# connector-bottom-j1-1.net
KiCad netlist of a schematic drawn in Altium Designer
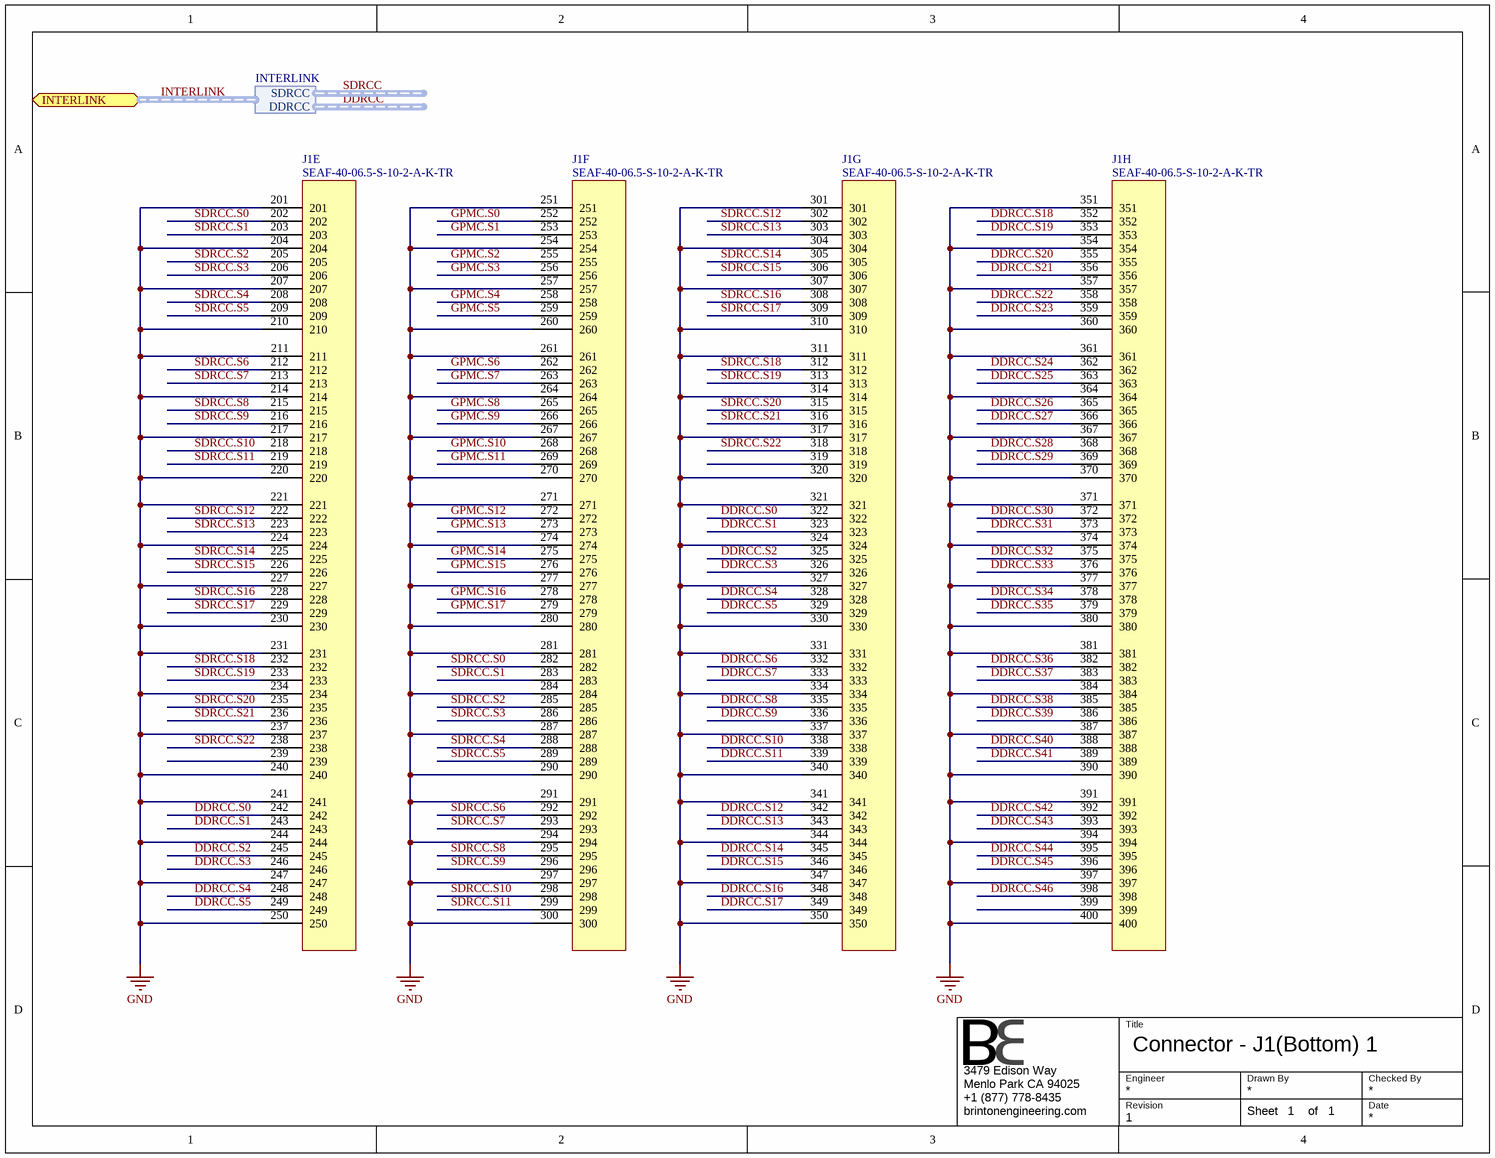
[diagram p0: connector-bottom-j1-1.SchDoc]

(export (version "E")
  (design (tool "Eeschema 10.0.6"))
  (components
    (comp (ref "J1")
      (value "SEAF-40-06.5-S-10-2-A-K-TR")
      (footprint "samtec:SEAF-40-06.5-S-10-2-A-K-TR")
      (description "Terminal Array Assembly, Surface Mount, 0.050\" Pitch, 400 Pins")
      (fields (field (name "MANUFACTURER") "Samtec"))
      (libsource (lib "samtec") (part "SEAF-40-06.5-S-10-2-A-K-TR"))
    )
  )
  (nets
    (net (code "3") (name "/DDRCC.S0") (class "Default")
      (node (ref "J1") (pin "242") (pinfunction "242_242") (pintype "passive"))
      (node (ref "J1") (pin "322") (pinfunction "322_322") (pintype "passive"))
    )
    (net (code "4") (name "/DDRCC.S1") (class "Default")
      (node (ref "J1") (pin "243") (pinfunction "243_243") (pintype "passive"))
      (node (ref "J1") (pin "323") (pinfunction "323_323") (pintype "passive"))
    )
    (net (code "5") (name "/DDRCC.S2") (class "Default")
      (node (ref "J1") (pin "245") (pinfunction "245_245") (pintype "passive"))
      (node (ref "J1") (pin "325") (pinfunction "325_325") (pintype "passive"))
    )
    (net (code "6") (name "/DDRCC.S3") (class "Default")
      (node (ref "J1") (pin "246") (pinfunction "246_246") (pintype "passive"))
      (node (ref "J1") (pin "326") (pinfunction "326_326") (pintype "passive"))
    )
    (net (code "7") (name "/DDRCC.S4") (class "Default")
      (node (ref "J1") (pin "248") (pinfunction "248_248") (pintype "passive"))
      (node (ref "J1") (pin "328") (pinfunction "328_328") (pintype "passive"))
    )
    (net (code "8") (name "/DDRCC.S5") (class "Default")
      (node (ref "J1") (pin "249") (pinfunction "249_249") (pintype "passive"))
      (node (ref "J1") (pin "329") (pinfunction "329_329") (pintype "passive"))
    )
    (net (code "9") (name "/DDRCC.S6") (class "Default")
      (node (ref "J1") (pin "332") (pinfunction "332_332") (pintype "passive"))
    )
    (net (code "10") (name "/DDRCC.S7") (class "Default")
      (node (ref "J1") (pin "333") (pinfunction "333_333") (pintype "passive"))
    )
    (net (code "11") (name "/DDRCC.S8") (class "Default")
      (node (ref "J1") (pin "335") (pinfunction "335_335") (pintype "passive"))
    )
    (net (code "12") (name "/DDRCC.S9") (class "Default")
      (node (ref "J1") (pin "336") (pinfunction "336_336") (pintype "passive"))
    )
    (net (code "13") (name "/DDRCC.S10") (class "Default")
      (node (ref "J1") (pin "338") (pinfunction "338_338") (pintype "passive"))
    )
    (net (code "14") (name "/DDRCC.S11") (class "Default")
      (node (ref "J1") (pin "339") (pinfunction "339_339") (pintype "passive"))
    )
    (net (code "15") (name "/DDRCC.S12") (class "Default")
      (node (ref "J1") (pin "342") (pinfunction "342_342") (pintype "passive"))
    )
    (net (code "16") (name "/DDRCC.S13") (class "Default")
      (node (ref "J1") (pin "343") (pinfunction "343_343") (pintype "passive"))
    )
    (net (code "17") (name "/DDRCC.S14") (class "Default")
      (node (ref "J1") (pin "345") (pinfunction "345_345") (pintype "passive"))
    )
    (net (code "18") (name "/DDRCC.S15") (class "Default")
      (node (ref "J1") (pin "346") (pinfunction "346_346") (pintype "passive"))
    )
    (net (code "19") (name "/DDRCC.S16") (class "Default")
      (node (ref "J1") (pin "348") (pinfunction "348_348") (pintype "passive"))
    )
    (net (code "20") (name "/DDRCC.S17") (class "Default")
      (node (ref "J1") (pin "349") (pinfunction "349_349") (pintype "passive"))
    )
    (net (code "21") (name "/DDRCC.S18") (class "Default")
      (node (ref "J1") (pin "352") (pinfunction "352_352") (pintype "passive"))
    )
    (net (code "22") (name "/DDRCC.S19") (class "Default")
      (node (ref "J1") (pin "353") (pinfunction "353_353") (pintype "passive"))
    )
    (net (code "23") (name "/DDRCC.S20") (class "Default")
      (node (ref "J1") (pin "355") (pinfunction "355_355") (pintype "passive"))
    )
    (net (code "24") (name "/DDRCC.S21") (class "Default")
      (node (ref "J1") (pin "356") (pinfunction "356_356") (pintype "passive"))
    )
    (net (code "25") (name "/DDRCC.S22") (class "Default")
      (node (ref "J1") (pin "358") (pinfunction "358_358") (pintype "passive"))
    )
    (net (code "26") (name "/DDRCC.S23") (class "Default")
      (node (ref "J1") (pin "359") (pinfunction "359_359") (pintype "passive"))
    )
    (net (code "27") (name "/DDRCC.S24") (class "Default")
      (node (ref "J1") (pin "362") (pinfunction "362_362") (pintype "passive"))
    )
    (net (code "28") (name "/DDRCC.S25") (class "Default")
      (node (ref "J1") (pin "363") (pinfunction "363_363") (pintype "passive"))
    )
    (net (code "29") (name "/DDRCC.S26") (class "Default")
      (node (ref "J1") (pin "365") (pinfunction "365_365") (pintype "passive"))
    )
    (net (code "30") (name "/DDRCC.S27") (class "Default")
      (node (ref "J1") (pin "366") (pinfunction "366_366") (pintype "passive"))
    )
    (net (code "31") (name "/DDRCC.S28") (class "Default")
      (node (ref "J1") (pin "368") (pinfunction "368_368") (pintype "passive"))
    )
    (net (code "32") (name "/DDRCC.S29") (class "Default")
      (node (ref "J1") (pin "369") (pinfunction "369_369") (pintype "passive"))
    )
    (net (code "33") (name "/DDRCC.S30") (class "Default")
      (node (ref "J1") (pin "372") (pinfunction "372_372") (pintype "passive"))
    )
    (net (code "34") (name "/DDRCC.S31") (class "Default")
      (node (ref "J1") (pin "373") (pinfunction "373_373") (pintype "passive"))
    )
    (net (code "35") (name "/DDRCC.S32") (class "Default")
      (node (ref "J1") (pin "375") (pinfunction "375_375") (pintype "passive"))
    )
    (net (code "36") (name "/DDRCC.S33") (class "Default")
      (node (ref "J1") (pin "376") (pinfunction "376_376") (pintype "passive"))
    )
    (net (code "37") (name "/DDRCC.S34") (class "Default")
      (node (ref "J1") (pin "378") (pinfunction "378_378") (pintype "passive"))
    )
    (net (code "38") (name "/DDRCC.S35") (class "Default")
      (node (ref "J1") (pin "379") (pinfunction "379_379") (pintype "passive"))
    )
    (net (code "39") (name "/DDRCC.S36") (class "Default")
      (node (ref "J1") (pin "382") (pinfunction "382_382") (pintype "passive"))
    )
    (net (code "40") (name "/DDRCC.S37") (class "Default")
      (node (ref "J1") (pin "383") (pinfunction "383_383") (pintype "passive"))
    )
    (net (code "41") (name "/DDRCC.S38") (class "Default")
      (node (ref "J1") (pin "385") (pinfunction "385_385") (pintype "passive"))
    )
    (net (code "42") (name "/DDRCC.S39") (class "Default")
      (node (ref "J1") (pin "386") (pinfunction "386_386") (pintype "passive"))
    )
    (net (code "43") (name "/DDRCC.S40") (class "Default")
      (node (ref "J1") (pin "388") (pinfunction "388_388") (pintype "passive"))
    )
    (net (code "44") (name "/DDRCC.S41") (class "Default")
      (node (ref "J1") (pin "389") (pinfunction "389_389") (pintype "passive"))
    )
    (net (code "45") (name "/DDRCC.S42") (class "Default")
      (node (ref "J1") (pin "392") (pinfunction "392_392") (pintype "passive"))
    )
    (net (code "46") (name "/DDRCC.S43") (class "Default")
      (node (ref "J1") (pin "393") (pinfunction "393_393") (pintype "passive"))
    )
    (net (code "47") (name "/DDRCC.S44") (class "Default")
      (node (ref "J1") (pin "395") (pinfunction "395_395") (pintype "passive"))
    )
    (net (code "48") (name "/DDRCC.S45") (class "Default")
      (node (ref "J1") (pin "396") (pinfunction "396_396") (pintype "passive"))
    )
    (net (code "49") (name "/DDRCC.S46") (class "Default")
      (node (ref "J1") (pin "398") (pinfunction "398_398") (pintype "passive"))
    )
    (net (code "51") (name "/GPMC.S0") (class "Default")
      (node (ref "J1") (pin "252") (pinfunction "252_252") (pintype "passive"))
    )
    (net (code "52") (name "/GPMC.S1") (class "Default")
      (node (ref "J1") (pin "253") (pinfunction "253_253") (pintype "passive"))
    )
    (net (code "53") (name "/GPMC.S2") (class "Default")
      (node (ref "J1") (pin "255") (pinfunction "255_255") (pintype "passive"))
    )
    (net (code "54") (name "/GPMC.S3") (class "Default")
      (node (ref "J1") (pin "256") (pinfunction "256_256") (pintype "passive"))
    )
    (net (code "55") (name "/GPMC.S4") (class "Default")
      (node (ref "J1") (pin "258") (pinfunction "258_258") (pintype "passive"))
    )
    (net (code "56") (name "/GPMC.S5") (class "Default")
      (node (ref "J1") (pin "259") (pinfunction "259_259") (pintype "passive"))
    )
    (net (code "57") (name "/GPMC.S6") (class "Default")
      (node (ref "J1") (pin "262") (pinfunction "262_262") (pintype "passive"))
    )
    (net (code "58") (name "/GPMC.S7") (class "Default")
      (node (ref "J1") (pin "263") (pinfunction "263_263") (pintype "passive"))
    )
    (net (code "59") (name "/GPMC.S8") (class "Default")
      (node (ref "J1") (pin "265") (pinfunction "265_265") (pintype "passive"))
    )
    (net (code "60") (name "/GPMC.S9") (class "Default")
      (node (ref "J1") (pin "266") (pinfunction "266_266") (pintype "passive"))
    )
    (net (code "61") (name "/GPMC.S10") (class "Default")
      (node (ref "J1") (pin "268") (pinfunction "268_268") (pintype "passive"))
    )
    (net (code "62") (name "/GPMC.S11") (class "Default")
      (node (ref "J1") (pin "269") (pinfunction "269_269") (pintype "passive"))
    )
    (net (code "63") (name "/GPMC.S12") (class "Default")
      (node (ref "J1") (pin "272") (pinfunction "272_272") (pintype "passive"))
    )
    (net (code "64") (name "/GPMC.S13") (class "Default")
      (node (ref "J1") (pin "273") (pinfunction "273_273") (pintype "passive"))
    )
    (net (code "65") (name "/GPMC.S14") (class "Default")
      (node (ref "J1") (pin "275") (pinfunction "275_275") (pintype "passive"))
    )
    (net (code "66") (name "/GPMC.S15") (class "Default")
      (node (ref "J1") (pin "276") (pinfunction "276_276") (pintype "passive"))
    )
    (net (code "67") (name "/GPMC.S16") (class "Default")
      (node (ref "J1") (pin "278") (pinfunction "278_278") (pintype "passive"))
    )
    (net (code "68") (name "/GPMC.S17") (class "Default")
      (node (ref "J1") (pin "279") (pinfunction "279_279") (pintype "passive"))
    )
    (net (code "69") (name "/SDRCC.S0") (class "Default")
      (node (ref "J1") (pin "202") (pinfunction "202_202") (pintype "passive"))
      (node (ref "J1") (pin "282") (pinfunction "282_282") (pintype "passive"))
    )
    (net (code "70") (name "/SDRCC.S1") (class "Default")
      (node (ref "J1") (pin "203") (pinfunction "203_203") (pintype "passive"))
      (node (ref "J1") (pin "283") (pinfunction "283_283") (pintype "passive"))
    )
    (net (code "71") (name "/SDRCC.S2") (class "Default")
      (node (ref "J1") (pin "205") (pinfunction "205_205") (pintype "passive"))
      (node (ref "J1") (pin "285") (pinfunction "285_285") (pintype "passive"))
    )
    (net (code "72") (name "/SDRCC.S3") (class "Default")
      (node (ref "J1") (pin "206") (pinfunction "206_206") (pintype "passive"))
      (node (ref "J1") (pin "286") (pinfunction "286_286") (pintype "passive"))
    )
    (net (code "73") (name "/SDRCC.S4") (class "Default")
      (node (ref "J1") (pin "208") (pinfunction "208_208") (pintype "passive"))
      (node (ref "J1") (pin "288") (pinfunction "288_288") (pintype "passive"))
    )
    (net (code "74") (name "/SDRCC.S5") (class "Default")
      (node (ref "J1") (pin "209") (pinfunction "209_209") (pintype "passive"))
      (node (ref "J1") (pin "289") (pinfunction "289_289") (pintype "passive"))
    )
    (net (code "75") (name "/SDRCC.S6") (class "Default")
      (node (ref "J1") (pin "212") (pinfunction "212_212") (pintype "passive"))
      (node (ref "J1") (pin "292") (pinfunction "292_292") (pintype "passive"))
    )
    (net (code "76") (name "/SDRCC.S7") (class "Default")
      (node (ref "J1") (pin "213") (pinfunction "213_213") (pintype "passive"))
      (node (ref "J1") (pin "293") (pinfunction "293_293") (pintype "passive"))
    )
    (net (code "77") (name "/SDRCC.S8") (class "Default")
      (node (ref "J1") (pin "215") (pinfunction "215_215") (pintype "passive"))
      (node (ref "J1") (pin "295") (pinfunction "295_295") (pintype "passive"))
    )
    (net (code "78") (name "/SDRCC.S9") (class "Default")
      (node (ref "J1") (pin "216") (pinfunction "216_216") (pintype "passive"))
      (node (ref "J1") (pin "296") (pinfunction "296_296") (pintype "passive"))
    )
    (net (code "79") (name "/SDRCC.S10") (class "Default")
      (node (ref "J1") (pin "218") (pinfunction "218_218") (pintype "passive"))
      (node (ref "J1") (pin "298") (pinfunction "298_298") (pintype "passive"))
    )
    (net (code "80") (name "/SDRCC.S11") (class "Default")
      (node (ref "J1") (pin "219") (pinfunction "219_219") (pintype "passive"))
      (node (ref "J1") (pin "299") (pinfunction "299_299") (pintype "passive"))
    )
    (net (code "81") (name "/SDRCC.S12") (class "Default")
      (node (ref "J1") (pin "222") (pinfunction "222_222") (pintype "passive"))
      (node (ref "J1") (pin "302") (pinfunction "302_302") (pintype "passive"))
    )
    (net (code "82") (name "/SDRCC.S13") (class "Default")
      (node (ref "J1") (pin "223") (pinfunction "223_223") (pintype "passive"))
      (node (ref "J1") (pin "303") (pinfunction "303_303") (pintype "passive"))
    )
    (net (code "83") (name "/SDRCC.S14") (class "Default")
      (node (ref "J1") (pin "225") (pinfunction "225_225") (pintype "passive"))
      (node (ref "J1") (pin "305") (pinfunction "305_305") (pintype "passive"))
    )
    (net (code "84") (name "/SDRCC.S15") (class "Default")
      (node (ref "J1") (pin "226") (pinfunction "226_226") (pintype "passive"))
      (node (ref "J1") (pin "306") (pinfunction "306_306") (pintype "passive"))
    )
    (net (code "85") (name "/SDRCC.S16") (class "Default")
      (node (ref "J1") (pin "228") (pinfunction "228_228") (pintype "passive"))
      (node (ref "J1") (pin "308") (pinfunction "308_308") (pintype "passive"))
    )
    (net (code "86") (name "/SDRCC.S17") (class "Default")
      (node (ref "J1") (pin "229") (pinfunction "229_229") (pintype "passive"))
      (node (ref "J1") (pin "309") (pinfunction "309_309") (pintype "passive"))
    )
    (net (code "87") (name "/SDRCC.S18") (class "Default")
      (node (ref "J1") (pin "232") (pinfunction "232_232") (pintype "passive"))
      (node (ref "J1") (pin "312") (pinfunction "312_312") (pintype "passive"))
    )
    (net (code "88") (name "/SDRCC.S19") (class "Default")
      (node (ref "J1") (pin "233") (pinfunction "233_233") (pintype "passive"))
      (node (ref "J1") (pin "313") (pinfunction "313_313") (pintype "passive"))
    )
    (net (code "89") (name "/SDRCC.S20") (class "Default")
      (node (ref "J1") (pin "235") (pinfunction "235_235") (pintype "passive"))
      (node (ref "J1") (pin "315") (pinfunction "315_315") (pintype "passive"))
    )
    (net (code "90") (name "/SDRCC.S21") (class "Default")
      (node (ref "J1") (pin "236") (pinfunction "236_236") (pintype "passive"))
      (node (ref "J1") (pin "316") (pinfunction "316_316") (pintype "passive"))
    )
    (net (code "91") (name "/SDRCC.S22") (class "Default")
      (node (ref "J1") (pin "238") (pinfunction "238_238") (pintype "passive"))
      (node (ref "J1") (pin "318") (pinfunction "318_318") (pintype "passive"))
    )
    (net (code "93") (name "GND") (class "Default")
      (node (ref "J1") (pin "201") (pinfunction "201_201") (pintype "passive"))
      (node (ref "J1") (pin "204") (pinfunction "204_204") (pintype "passive"))
      (node (ref "J1") (pin "207") (pinfunction "207_207") (pintype "passive"))
      (node (ref "J1") (pin "210") (pinfunction "210_210") (pintype "passive"))
      (node (ref "J1") (pin "211") (pinfunction "211_211") (pintype "passive"))
      (node (ref "J1") (pin "214") (pinfunction "214_214") (pintype "passive"))
      (node (ref "J1") (pin "217") (pinfunction "217_217") (pintype "passive"))
      (node (ref "J1") (pin "220") (pinfunction "220_220") (pintype "passive"))
      (node (ref "J1") (pin "221") (pinfunction "221_221") (pintype "passive"))
      (node (ref "J1") (pin "224") (pinfunction "224_224") (pintype "passive"))
      (node (ref "J1") (pin "227") (pinfunction "227_227") (pintype "passive"))
      (node (ref "J1") (pin "230") (pinfunction "230_230") (pintype "passive"))
      (node (ref "J1") (pin "231") (pinfunction "231_231") (pintype "passive"))
      (node (ref "J1") (pin "234") (pinfunction "234_234") (pintype "passive"))
      (node (ref "J1") (pin "237") (pinfunction "237_237") (pintype "passive"))
      (node (ref "J1") (pin "240") (pinfunction "240_240") (pintype "passive"))
      (node (ref "J1") (pin "241") (pinfunction "241_241") (pintype "passive"))
      (node (ref "J1") (pin "244") (pinfunction "244_244") (pintype "passive"))
      (node (ref "J1") (pin "247") (pinfunction "247_247") (pintype "passive"))
      (node (ref "J1") (pin "250") (pinfunction "250_250") (pintype "passive"))
      (node (ref "J1") (pin "251") (pinfunction "251_251") (pintype "passive"))
      (node (ref "J1") (pin "254") (pinfunction "254_254") (pintype "passive"))
      (node (ref "J1") (pin "257") (pinfunction "257_257") (pintype "passive"))
      (node (ref "J1") (pin "260") (pinfunction "260_260") (pintype "passive"))
      (node (ref "J1") (pin "261") (pinfunction "261_261") (pintype "passive"))
      (node (ref "J1") (pin "264") (pinfunction "264_264") (pintype "passive"))
      (node (ref "J1") (pin "267") (pinfunction "267_267") (pintype "passive"))
      (node (ref "J1") (pin "270") (pinfunction "270_270") (pintype "passive"))
      (node (ref "J1") (pin "271") (pinfunction "271_271") (pintype "passive"))
      (node (ref "J1") (pin "274") (pinfunction "274_274") (pintype "passive"))
      (node (ref "J1") (pin "277") (pinfunction "277_277") (pintype "passive"))
      (node (ref "J1") (pin "280") (pinfunction "280_280") (pintype "passive"))
      (node (ref "J1") (pin "281") (pinfunction "281_281") (pintype "passive"))
      (node (ref "J1") (pin "284") (pinfunction "284_284") (pintype "passive"))
      (node (ref "J1") (pin "287") (pinfunction "287_287") (pintype "passive"))
      (node (ref "J1") (pin "290") (pinfunction "290_290") (pintype "passive"))
      (node (ref "J1") (pin "291") (pinfunction "291_291") (pintype "passive"))
      (node (ref "J1") (pin "294") (pinfunction "294_294") (pintype "passive"))
      (node (ref "J1") (pin "297") (pinfunction "297_297") (pintype "passive"))
      (node (ref "J1") (pin "300") (pinfunction "300_300") (pintype "passive"))
      (node (ref "J1") (pin "301") (pinfunction "301_301") (pintype "passive"))
      (node (ref "J1") (pin "304") (pinfunction "304_304") (pintype "passive"))
      (node (ref "J1") (pin "307") (pinfunction "307_307") (pintype "passive"))
      (node (ref "J1") (pin "310") (pinfunction "310_310") (pintype "passive"))
      (node (ref "J1") (pin "311") (pinfunction "311_311") (pintype "passive"))
      (node (ref "J1") (pin "314") (pinfunction "314_314") (pintype "passive"))
      (node (ref "J1") (pin "317") (pinfunction "317_317") (pintype "passive"))
      (node (ref "J1") (pin "320") (pinfunction "320_320") (pintype "passive"))
      (node (ref "J1") (pin "321") (pinfunction "321_321") (pintype "passive"))
      (node (ref "J1") (pin "324") (pinfunction "324_324") (pintype "passive"))
      (node (ref "J1") (pin "327") (pinfunction "327_327") (pintype "passive"))
      (node (ref "J1") (pin "330") (pinfunction "330_330") (pintype "passive"))
      (node (ref "J1") (pin "331") (pinfunction "331_331") (pintype "passive"))
      (node (ref "J1") (pin "334") (pinfunction "334_334") (pintype "passive"))
      (node (ref "J1") (pin "337") (pinfunction "337_337") (pintype "passive"))
      (node (ref "J1") (pin "340") (pinfunction "340_340") (pintype "passive"))
      (node (ref "J1") (pin "341") (pinfunction "341_341") (pintype "passive"))
      (node (ref "J1") (pin "344") (pinfunction "344_344") (pintype "passive"))
      (node (ref "J1") (pin "347") (pinfunction "347_347") (pintype "passive"))
      (node (ref "J1") (pin "350") (pinfunction "350_350") (pintype "passive"))
      (node (ref "J1") (pin "351") (pinfunction "351_351") (pintype "passive"))
      (node (ref "J1") (pin "354") (pinfunction "354_354") (pintype "passive"))
      (node (ref "J1") (pin "357") (pinfunction "357_357") (pintype "passive"))
      (node (ref "J1") (pin "360") (pinfunction "360_360") (pintype "passive"))
      (node (ref "J1") (pin "361") (pinfunction "361_361") (pintype "passive"))
      (node (ref "J1") (pin "364") (pinfunction "364_364") (pintype "passive"))
      (node (ref "J1") (pin "367") (pinfunction "367_367") (pintype "passive"))
      (node (ref "J1") (pin "370") (pinfunction "370_370") (pintype "passive"))
      (node (ref "J1") (pin "371") (pinfunction "371_371") (pintype "passive"))
      (node (ref "J1") (pin "374") (pinfunction "374_374") (pintype "passive"))
      (node (ref "J1") (pin "377") (pinfunction "377_377") (pintype "passive"))
      (node (ref "J1") (pin "380") (pinfunction "380_380") (pintype "passive"))
      (node (ref "J1") (pin "381") (pinfunction "381_381") (pintype "passive"))
      (node (ref "J1") (pin "384") (pinfunction "384_384") (pintype "passive"))
      (node (ref "J1") (pin "387") (pinfunction "387_387") (pintype "passive"))
      (node (ref "J1") (pin "390") (pinfunction "390_390") (pintype "passive"))
      (node (ref "J1") (pin "391") (pinfunction "391_391") (pintype "passive"))
      (node (ref "J1") (pin "394") (pinfunction "394_394") (pintype "passive"))
      (node (ref "J1") (pin "397") (pinfunction "397_397") (pintype "passive"))
      (node (ref "J1") (pin "400") (pinfunction "400_400") (pintype "passive"))
    )
    (net (code "94") (name "unconnected-(J1-Pad239)") (class "Default")
      (node (ref "J1") (pin "239") (pinfunction "239_239") (pintype "passive"))
    )
    (net (code "95") (name "unconnected-(J1-Pad319)") (class "Default")
      (node (ref "J1") (pin "319") (pinfunction "319_319") (pintype "passive"))
    )
    (net (code "96") (name "unconnected-(J1-Pad399)") (class "Default")
      (node (ref "J1") (pin "399") (pinfunction "399_399") (pintype "passive"))
    )
  )
)
